# 010_Current_Sensor.net
KiCad netlist of a schematic drawn in Altium Designer
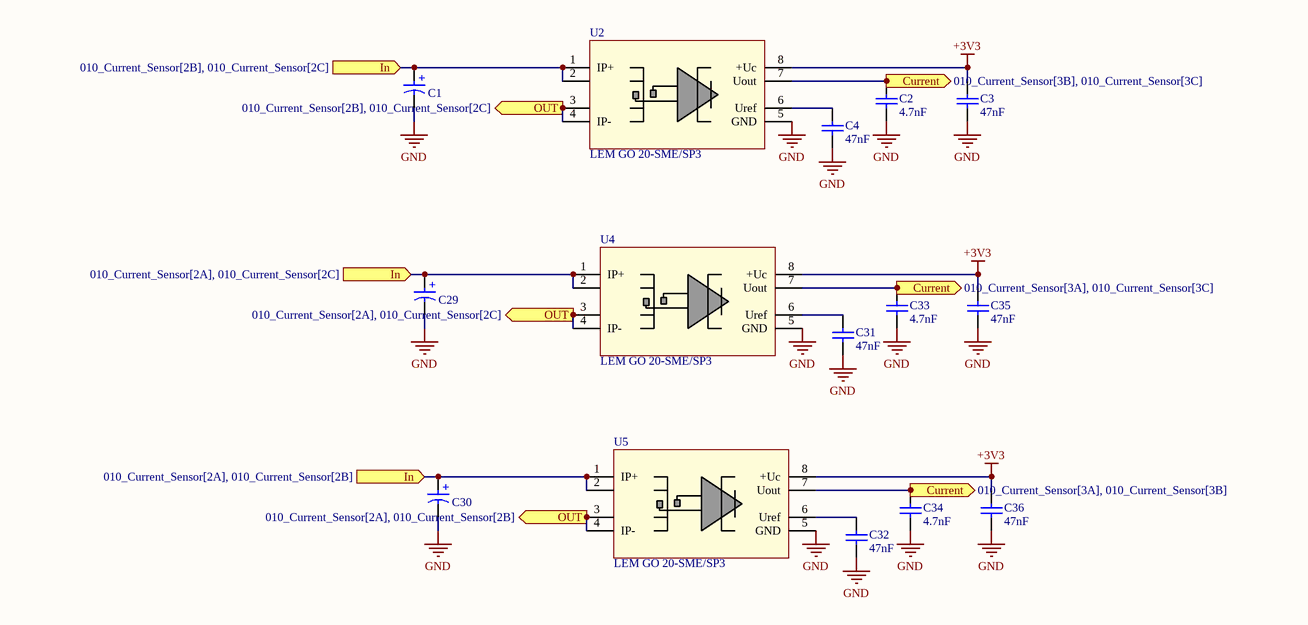
[diagram p0: 010_Current_Sensor.SchDoc]

(export (version "E")
  (design (tool "Eeschema 10.0.6"))
  (components
    (comp (ref "C1")
      (value "68µF")
      (footprint "WCAP-PSLC_D10H12.4")
      (description "WCAP-PSLC Aluminum Polymer Capacitor, V-Chip SMT, D10 x H12.4mm, 68µF, 50V")
      (fields
        (field (name "MANUFACTURER PART NUMBER") "875075761007")
        (field (name "MANUFACTURER") "Wurth Elektronik")
      )
      (libsource (lib "Altium_WCAP-PSLC (rev22c)") (part "875075761007"))
    )
    (comp (ref "C2")
      (value "4.7nF")
      (footprint "WCAP-CSGP_0805_L2W1.25H0.8_Reflow")
      (description "WCAP-CSGP Multilayer Ceramic Chip Capacitor, General Purpose, size 0805, X7R, 4.7nF, 50VDC")
      (fields
        (field (name "MANUFACTURER PART NUMBER") "885012207090")
        (field (name "MANUFACTURER") "Wurth Elektronik")
        (field (name "CAPACITANCE") "4.7nF")
      )
      (libsource (lib "Altium_WCAP-CSGP (rev22f)") (part "885012207090"))
    )
    (comp (ref "C3")
      (value "47nF")
      (footprint "WCAP-CSGP_0805_L2W1.25H0.8_Reflow")
      (description "WCAP-CSGP Multilayer Ceramic Chip Capacitor, General Purpose, size 0805, X7R, 47nF, 50VDC")
      (fields
        (field (name "MANUFACTURER PART NUMBER") "885012207096")
        (field (name "MANUFACTURER") "Wurth Elektronik")
        (field (name "CAPACITANCE") "47nF")
      )
      (libsource (lib "Altium_WCAP-CSGP (rev22f)") (part "885012207096"))
    )
    (comp (ref "C4")
      (value "47nF")
      (footprint "WCAP-CSGP_0805_L2W1.25H0.8_Reflow")
      (description "WCAP-CSGP Multilayer Ceramic Chip Capacitor, General Purpose, size 0805, X7R, 47nF, 50VDC")
      (fields
        (field (name "MANUFACTURER PART NUMBER") "885012207096")
        (field (name "MANUFACTURER") "Wurth Elektronik")
        (field (name "CAPACITANCE") "47nF")
      )
      (libsource (lib "Altium_WCAP-CSGP (rev22f)") (part "885012207096"))
    )
    (comp (ref "C29")
      (value "68µF")
      (footprint "WCAP-PSLC_D10H12.4")
      (description "WCAP-PSLC Aluminum Polymer Capacitor, V-Chip SMT, D10 x H12.4mm, 68µF, 50V")
      (fields
        (field (name "MANUFACTURER PART NUMBER") "875075761007")
        (field (name "MANUFACTURER") "Wurth Elektronik")
      )
      (libsource (lib "Altium_WCAP-PSLC (rev22c)") (part "875075761007"))
    )
    (comp (ref "C30")
      (value "68µF")
      (footprint "WCAP-PSLC_D10H12.4")
      (description "WCAP-PSLC Aluminum Polymer Capacitor, V-Chip SMT, D10 x H12.4mm, 68µF, 50V")
      (fields
        (field (name "MANUFACTURER PART NUMBER") "875075761007")
        (field (name "MANUFACTURER") "Wurth Elektronik")
      )
      (libsource (lib "Altium_WCAP-PSLC (rev22c)") (part "875075761007"))
    )
    (comp (ref "C31")
      (value "47nF")
      (footprint "WCAP-CSGP_0805_L2W1.25H0.8_Reflow")
      (description "WCAP-CSGP Multilayer Ceramic Chip Capacitor, General Purpose, size 0805, X7R, 47nF, 50VDC")
      (fields
        (field (name "MANUFACTURER PART NUMBER") "885012207096")
        (field (name "MANUFACTURER") "Wurth Elektronik")
        (field (name "CAPACITANCE") "47nF")
      )
      (libsource (lib "Altium_WCAP-CSGP (rev22f)") (part "885012207096"))
    )
    (comp (ref "C32")
      (value "47nF")
      (footprint "WCAP-CSGP_0805_L2W1.25H0.8_Reflow")
      (description "WCAP-CSGP Multilayer Ceramic Chip Capacitor, General Purpose, size 0805, X7R, 47nF, 50VDC")
      (fields
        (field (name "MANUFACTURER PART NUMBER") "885012207096")
        (field (name "MANUFACTURER") "Wurth Elektronik")
        (field (name "CAPACITANCE") "47nF")
      )
      (libsource (lib "Altium_WCAP-CSGP (rev22f)") (part "885012207096"))
    )
    (comp (ref "C33")
      (value "4.7nF")
      (footprint "WCAP-CSGP_0805_L2W1.25H0.8_Reflow")
      (description "WCAP-CSGP Multilayer Ceramic Chip Capacitor, General Purpose, size 0805, X7R, 4.7nF, 50VDC")
      (fields
        (field (name "MANUFACTURER PART NUMBER") "885012207090")
        (field (name "MANUFACTURER") "Wurth Elektronik")
        (field (name "CAPACITANCE") "4.7nF")
      )
      (libsource (lib "Altium_WCAP-CSGP (rev22f)") (part "885012207090"))
    )
    (comp (ref "C34")
      (value "4.7nF")
      (footprint "WCAP-CSGP_0805_L2W1.25H0.8_Reflow")
      (description "WCAP-CSGP Multilayer Ceramic Chip Capacitor, General Purpose, size 0805, X7R, 4.7nF, 50VDC")
      (fields
        (field (name "MANUFACTURER PART NUMBER") "885012207090")
        (field (name "MANUFACTURER") "Wurth Elektronik")
        (field (name "CAPACITANCE") "4.7nF")
      )
      (libsource (lib "Altium_WCAP-CSGP (rev22f)") (part "885012207090"))
    )
    (comp (ref "C35")
      (value "47nF")
      (footprint "WCAP-CSGP_0805_L2W1.25H0.8_Reflow")
      (description "WCAP-CSGP Multilayer Ceramic Chip Capacitor, General Purpose, size 0805, X7R, 47nF, 50VDC")
      (fields
        (field (name "MANUFACTURER PART NUMBER") "885012207096")
        (field (name "MANUFACTURER") "Wurth Elektronik")
        (field (name "CAPACITANCE") "47nF")
      )
      (libsource (lib "Altium_WCAP-CSGP (rev22f)") (part "885012207096"))
    )
    (comp (ref "C36")
      (value "47nF")
      (footprint "WCAP-CSGP_0805_L2W1.25H0.8_Reflow")
      (description "WCAP-CSGP Multilayer Ceramic Chip Capacitor, General Purpose, size 0805, X7R, 47nF, 50VDC")
      (fields
        (field (name "MANUFACTURER PART NUMBER") "885012207096")
        (field (name "MANUFACTURER") "Wurth Elektronik")
        (field (name "CAPACITANCE") "47nF")
      )
      (libsource (lib "Altium_WCAP-CSGP (rev22f)") (part "885012207096"))
    )
    (comp (ref "U2")
      (value "LEM GO 20-SME/SP3")
      (footprint "Lem_sme_SOIC8")
      (description "Integrated Current Transducer GO-SME s")
      (fields (field (name "MANUFACTURER") "LEM"))
      (libsource (lib "LEM_SME") (part "LEM_SME"))
    )
    (comp (ref "U4")
      (value "LEM GO 20-SME/SP3")
      (footprint "Lem_sme_SOIC8")
      (description "Integrated Current Transducer GO-SME s")
      (fields (field (name "MANUFACTURER") "LEM"))
      (libsource (lib "LEM_SME") (part "LEM_SME"))
    )
    (comp (ref "U5")
      (value "LEM GO 20-SME/SP3")
      (footprint "Lem_sme_SOIC8")
      (description "Integrated Current Transducer GO-SME s")
      (fields (field (name "MANUFACTURER") "LEM"))
      (libsource (lib "LEM_SME") (part "LEM_SME"))
    )
  )
  (nets
    (net (code "1") (name "+3V3") (class "Default")
      (node (ref "C3") (pin "2") (pinfunction "2_2") (pintype "passive"))
      (node (ref "C35") (pin "2") (pinfunction "2_2") (pintype "passive"))
      (node (ref "C36") (pin "2") (pinfunction "2_2") (pintype "passive"))
      (node (ref "U2") (pin "8") (pinfunction "+Uc_8") (pintype "passive"))
      (node (ref "U4") (pin "8") (pinfunction "+Uc_8") (pintype "passive"))
      (node (ref "U5") (pin "8") (pinfunction "+Uc_8") (pintype "passive"))
    )
    (net (code "2") (name "/Current") (class "Default")
      (node (ref "C2") (pin "2") (pinfunction "2_2") (pintype "passive"))
      (node (ref "C33") (pin "2") (pinfunction "2_2") (pintype "passive"))
      (node (ref "C34") (pin "2") (pinfunction "2_2") (pintype "passive"))
      (node (ref "U2") (pin "7") (pinfunction "Uout_7") (pintype "passive"))
      (node (ref "U4") (pin "7") (pinfunction "Uout_7") (pintype "passive"))
      (node (ref "U5") (pin "7") (pinfunction "Uout_7") (pintype "passive"))
    )
    (net (code "3") (name "/In") (class "Default")
      (node (ref "C1") (pin "1") (pinfunction "P_1") (pintype "passive"))
      (node (ref "C29") (pin "1") (pinfunction "P_1") (pintype "passive"))
      (node (ref "C30") (pin "1") (pinfunction "P_1") (pintype "passive"))
      (node (ref "U2") (pin "1") (pinfunction "IP+_1") (pintype "passive"))
      (node (ref "U2") (pin "2") (pintype "passive"))
      (node (ref "U4") (pin "1") (pinfunction "IP+_1") (pintype "passive"))
      (node (ref "U4") (pin "2") (pintype "passive"))
      (node (ref "U5") (pin "1") (pinfunction "IP+_1") (pintype "passive"))
      (node (ref "U5") (pin "2") (pintype "passive"))
    )
    (net (code "4") (name "/OUT") (class "Default")
      (node (ref "U2") (pin "3") (pintype "passive"))
      (node (ref "U2") (pin "4") (pinfunction "IP-_4") (pintype "passive"))
      (node (ref "U4") (pin "3") (pintype "passive"))
      (node (ref "U4") (pin "4") (pinfunction "IP-_4") (pintype "passive"))
      (node (ref "U5") (pin "3") (pintype "passive"))
      (node (ref "U5") (pin "4") (pinfunction "IP-_4") (pintype "passive"))
    )
    (net (code "5") (name "GND") (class "Default")
      (node (ref "C1") (pin "2") (pinfunction "N_2") (pintype "passive"))
      (node (ref "C2") (pin "1") (pinfunction "1_1") (pintype "passive"))
      (node (ref "C29") (pin "2") (pinfunction "N_2") (pintype "passive"))
      (node (ref "C3") (pin "1") (pinfunction "1_1") (pintype "passive"))
      (node (ref "C30") (pin "2") (pinfunction "N_2") (pintype "passive"))
      (node (ref "C31") (pin "1") (pinfunction "1_1") (pintype "passive"))
      (node (ref "C32") (pin "1") (pinfunction "1_1") (pintype "passive"))
      (node (ref "C33") (pin "1") (pinfunction "1_1") (pintype "passive"))
      (node (ref "C34") (pin "1") (pinfunction "1_1") (pintype "passive"))
      (node (ref "C35") (pin "1") (pinfunction "1_1") (pintype "passive"))
      (node (ref "C36") (pin "1") (pinfunction "1_1") (pintype "passive"))
      (node (ref "C4") (pin "1") (pinfunction "1_1") (pintype "passive"))
      (node (ref "U2") (pin "5") (pinfunction "GND_5") (pintype "passive"))
      (node (ref "U4") (pin "5") (pinfunction "GND_5") (pintype "passive"))
      (node (ref "U5") (pin "5") (pinfunction "GND_5") (pintype "passive"))
    )
    (net (code "6") (name "Net-(U2-Uref)") (class "Default")
      (node (ref "C4") (pin "2") (pinfunction "2_2") (pintype "passive"))
      (node (ref "U2") (pin "6") (pinfunction "Uref_6") (pintype "passive"))
    )
    (net (code "7") (name "Net-(U4-Uref)") (class "Default")
      (node (ref "C31") (pin "2") (pinfunction "2_2") (pintype "passive"))
      (node (ref "U4") (pin "6") (pinfunction "Uref_6") (pintype "passive"))
    )
    (net (code "8") (name "Net-(U5-Uref)") (class "Default")
      (node (ref "C32") (pin "2") (pinfunction "2_2") (pintype "passive"))
      (node (ref "U5") (pin "6") (pinfunction "Uref_6") (pintype "passive"))
    )
  )
)
